# design.net
KiCad netlist of a schematic drawn in Altium Designer
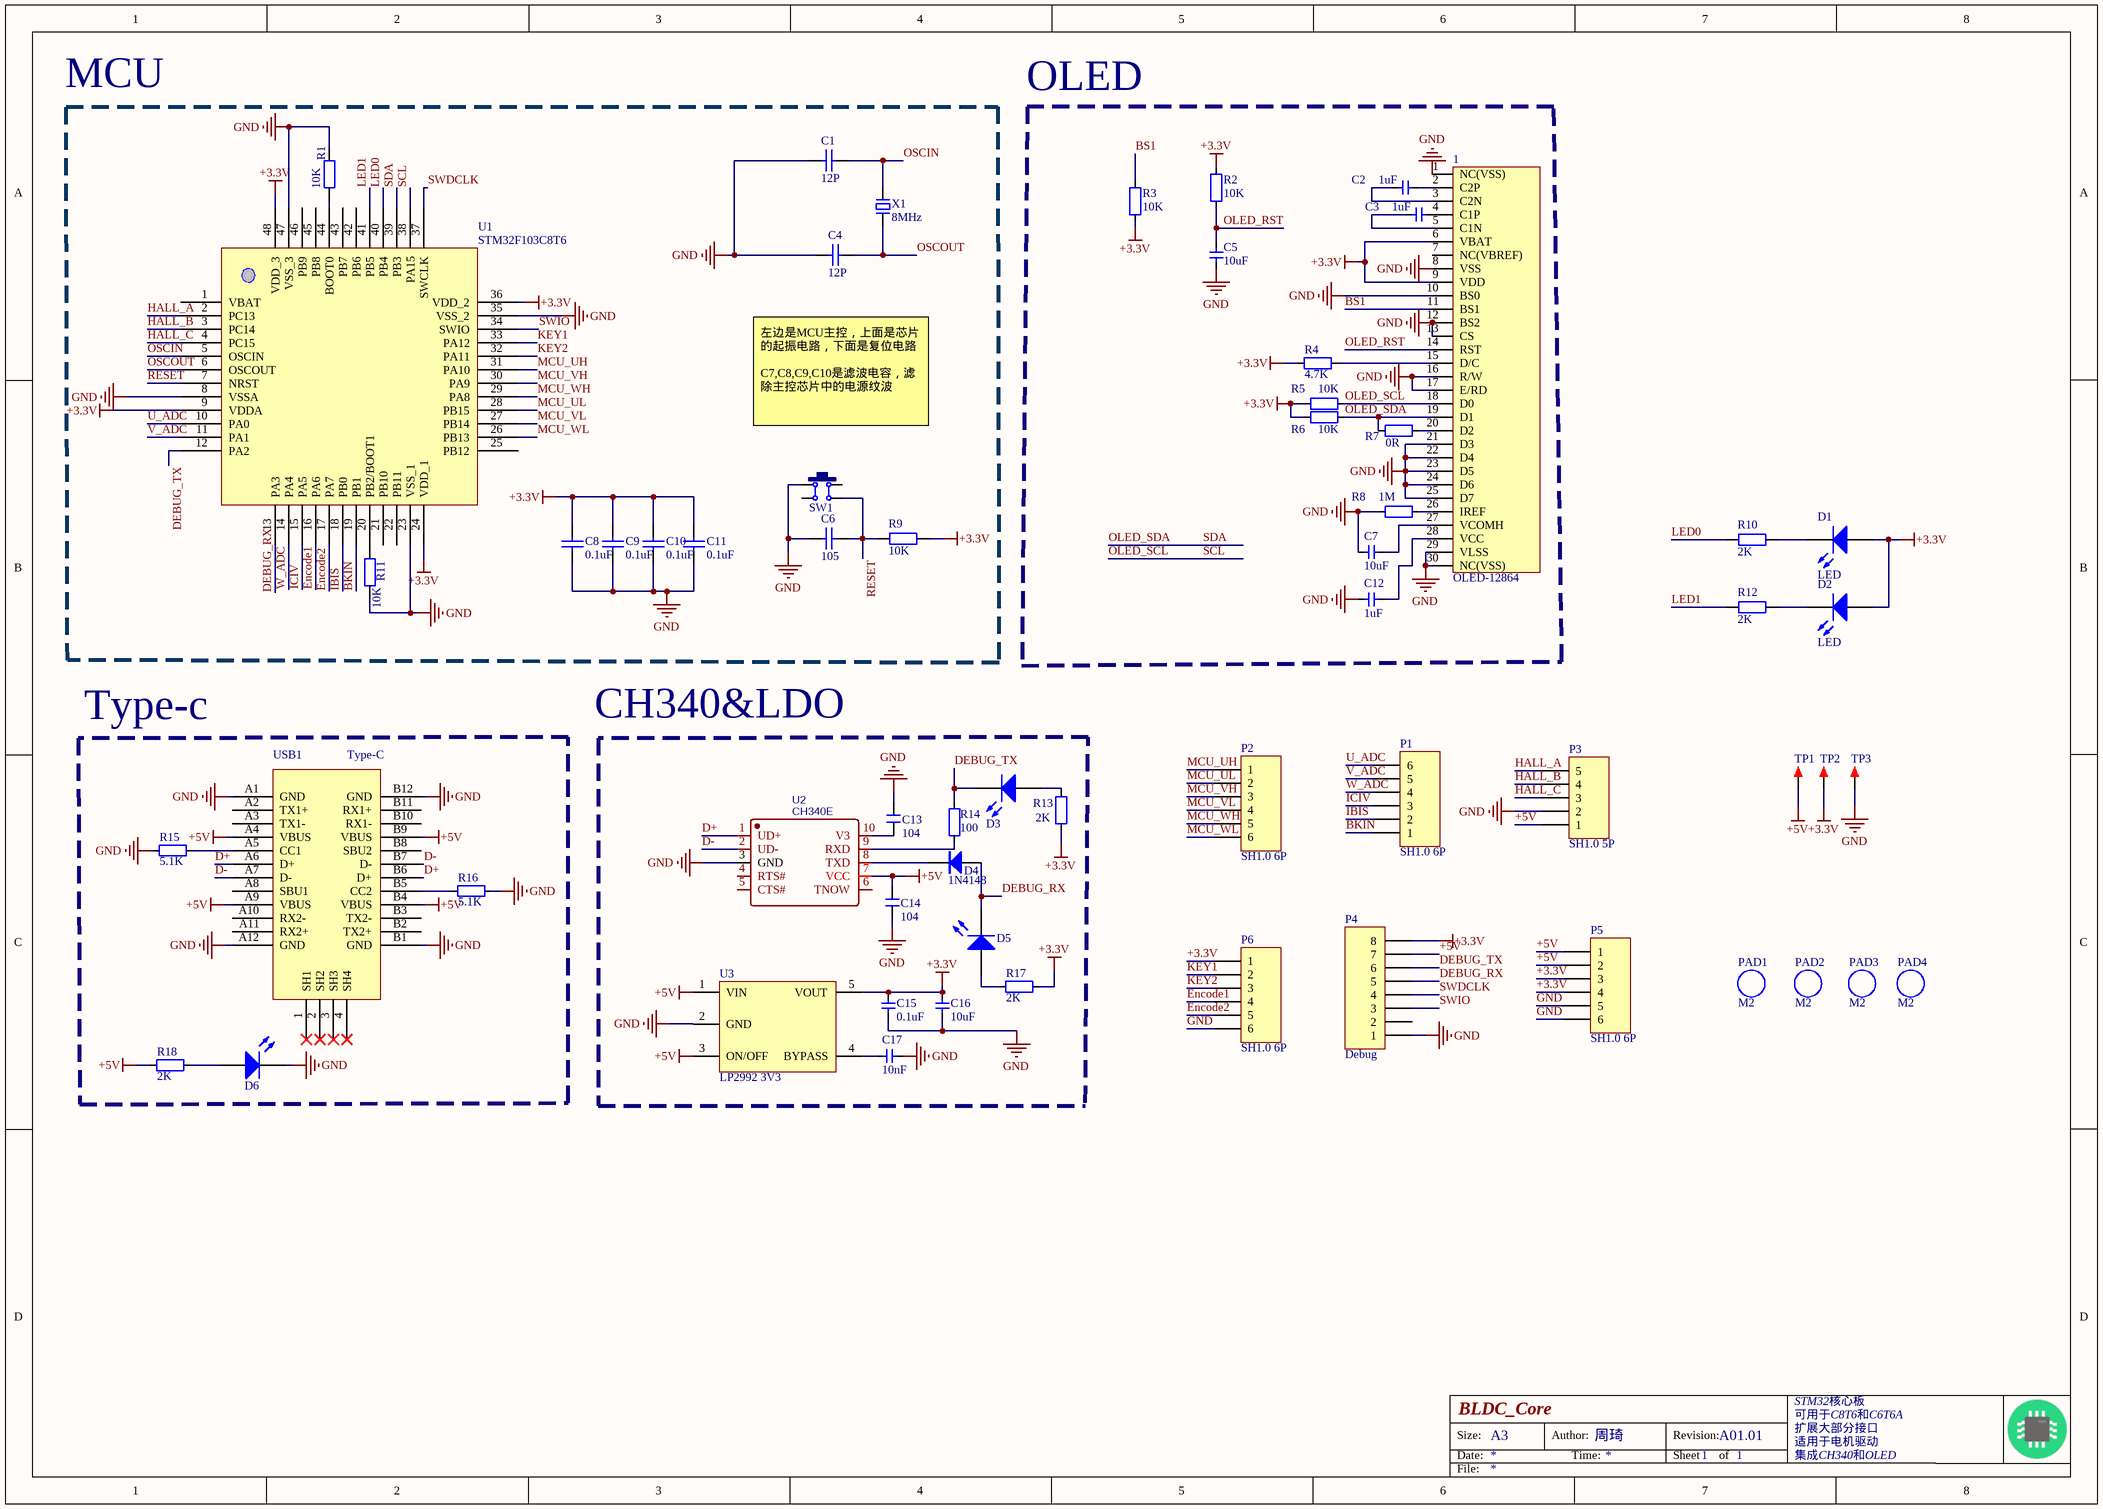
[diagram p0: 原理图.SchDoc]

(export (version "E")
  (design (tool "Eeschema 10.0.6"))
  (components
    (comp (ref "1")
      (value "OLED-12864")
      (footprint "OLED-12864-1.3-TOP")
      (description "显示屏")
      (libsource (lib "MyPcbLib") (part "OLED-12864"))
    )
    (comp (ref "C1")
      (value "12P")
      (footprint "C0603_M")
      (description "贴片电容")
      (libsource (lib "0.1 - 电阻-电容-电感-磁珠-电位器") (part "C"))
    )
    (comp (ref "C2")
      (value "1uF")
      (footprint "C0402_L")
      (description "Capacitor")
      (libsource (lib "MyPcbLib") (part "电容-0402"))
    )
    (comp (ref "C3")
      (value "1uF")
      (footprint "C0402_L")
      (description "Capacitor")
      (libsource (lib "MyPcbLib") (part "电容-0402"))
    )
    (comp (ref "C4")
      (value "12P")
      (footprint "C0603_M")
      (description "贴片电容")
      (libsource (lib "0.1 - 电阻-电容-电感-磁珠-电位器") (part "C"))
    )
    (comp (ref "C5")
      (value "10uF")
      (footprint "C0402_L")
      (description "Capacitor")
      (libsource (lib "MyPcbLib") (part "电容-0402"))
    )
    (comp (ref "C6")
      (value "105")
      (footprint "C0402_L")
      (description "贴片电容")
      (libsource (lib "0.1 - 电阻-电容-电感-磁珠-电位器") (part "C"))
    )
    (comp (ref "C7")
      (value "10uF")
      (footprint "C0402_L")
      (description "Capacitor")
      (libsource (lib "MyPcbLib") (part "电容-0402"))
    )
    (comp (ref "C8")
      (value "0.1uF")
      (footprint "C0402_L")
      (description "贴片电容")
      (libsource (lib "0.1 - 电阻-电容-电感-磁珠-电位器") (part "C"))
    )
    (comp (ref "C9")
      (value "0.1uF")
      (footprint "C0402_L")
      (description "贴片电容")
      (libsource (lib "0.1 - 电阻-电容-电感-磁珠-电位器") (part "C"))
    )
    (comp (ref "C10")
      (value "0.1uF")
      (footprint "C0402_L")
      (description "贴片电容")
      (libsource (lib "0.1 - 电阻-电容-电感-磁珠-电位器") (part "C"))
    )
    (comp (ref "C11")
      (value "0.1uF")
      (footprint "C0402_L")
      (description "贴片电容")
      (libsource (lib "0.1 - 电阻-电容-电感-磁珠-电位器") (part "C"))
    )
    (comp (ref "C12")
      (value "1uF")
      (footprint "C0402_L")
      (description "Capacitor")
      (libsource (lib "MyPcbLib") (part "电容-0402"))
    )
    (comp (ref "C13")
      (value "104")
      (footprint "C0402_L")
      (description "无极性贴片电容")
      (fields (field (name "版权归属") "源创客"))
      (libsource (lib "9-电阻-电容-电感") (part "C"))
    )
    (comp (ref "C14")
      (value "104")
      (footprint "C0402_L")
      (description "无极性贴片电容")
      (fields (field (name "版权归属") "源创客"))
      (libsource (lib "9-电阻-电容-电感") (part "C"))
    )
    (comp (ref "C15")
      (value "0.1uF")
      (footprint "C0402_L")
      (description "Capacitor")
      (libsource (lib "MyPcbLib") (part "电容-0402"))
    )
    (comp (ref "C16")
      (value "10uF")
      (footprint "C0402_L")
      (description "Capacitor")
      (libsource (lib "MyPcbLib") (part "电容-0402"))
    )
    (comp (ref "C17")
      (value "10nF")
      (footprint "C0402_L")
      (description "Capacitor")
      (libsource (lib "MyPcbLib") (part "电容-0402"))
    )
    (comp (ref "D1")
      (value "LED")
      (footprint "LED0603_B")
      (description "发光二极管")
      (libsource (lib "0.3 - LED发光二极管") (part "LED"))
    )
    (comp (ref "D2")
      (value "LED")
      (footprint "LED0603_B")
      (description "发光二极管")
      (libsource (lib "0.3 - LED发光二极管") (part "LED"))
    )
    (comp (ref "D3")
      (value "LED0")
      (footprint "LED0603_G")
      (description "发光二极管")
      (fields (field (name "PUBLISHER") "Altium Limited"))
      (libsource (lib "18-常用器件") (part "LED0"))
    )
    (comp (ref "D4")
      (value "1N4148")
      (footprint "SOD-123")
      (description "整流二极管")
      (fields (field (name "版权归属") "源创客"))
      (libsource (lib "10-二极管-整流桥") (part "M7"))
    )
    (comp (ref "D5")
      (value "LED0")
      (footprint "LED0603_G")
      (description "发光二极管")
      (fields (field (name "PUBLISHER") "Altium Limited"))
      (libsource (lib "18-常用器件") (part "LED0"))
    )
    (comp (ref "D6")
      (value "LED0")
      (footprint "LED0603_R")
      (description "发光二极管")
      (fields (field (name "PUBLISHER") "Altium Limited"))
      (libsource (lib "18-常用器件") (part "LED0"))
    )
    (comp (ref "P1")
      (value "SH1.0 6P")
      (footprint "SH 1.0-WS-6P")
      (description "Header, 6-Pin")
      (fields (field (name "PUBLISHER") "Altium Limited"))
      (libsource (lib "") (part "Header 6_1"))
    )
    (comp (ref "P2")
      (value "SH1.0 6P")
      (footprint "SH 1.0-WS-6P")
      (description "Header, 6-Pin")
      (fields (field (name "PUBLISHER") "Altium Limited"))
      (libsource (lib "Miscellaneous Connectors") (part "Header 6"))
    )
    (comp (ref "P3")
      (value "SH1.0 5P")
      (footprint "SH 1.0-LS-5P")
      (description "Header, 5-Pin")
      (fields (field (name "PUBLISHER") "Altium Limited"))
      (libsource (lib "Miscellaneous Connectors") (part "Header 5"))
    )
    (comp (ref "P4")
      (value "Debug")
      (footprint "FPC0.5 2H-WS-8P")
      (description "Header, 8-Pin")
      (fields (field (name "PUBLISHER") "Altium Limited"))
      (libsource (lib "Miscellaneous Connectors") (part "Header 8"))
    )
    (comp (ref "P5")
      (value "SH1.0 6P")
      (footprint "SH 1.0-WS-6P")
      (description "Header, 6-Pin")
      (fields (field (name "PUBLISHER") "Altium Limited"))
      (libsource (lib "Miscellaneous Connectors") (part "Header 6"))
    )
    (comp (ref "P6")
      (value "SH1.0 6P")
      (footprint "SH 1.0-WS-6P")
      (description "Header, 6-Pin")
      (fields (field (name "PUBLISHER") "Altium Limited"))
      (libsource (lib "Miscellaneous Connectors") (part "Header 6"))
    )
    (comp (ref "PAD1")
      (value "M2")
      (footprint "M2")
      (description "铜柱孔")
      (libsource (lib "0.7 - 常用按键-开关-蜂鸣器-电池-测试点") (part "M3"))
    )
    (comp (ref "PAD2")
      (value "M2")
      (footprint "M2")
      (description "铜柱孔")
      (libsource (lib "0.7 - 常用按键-开关-蜂鸣器-电池-测试点") (part "M3"))
    )
    (comp (ref "PAD3")
      (value "M2")
      (footprint "M2")
      (description "铜柱孔")
      (libsource (lib "0.7 - 常用按键-开关-蜂鸣器-电池-测试点") (part "M3"))
    )
    (comp (ref "PAD4")
      (value "M2")
      (footprint "M2")
      (description "铜柱孔")
      (libsource (lib "0.7 - 常用按键-开关-蜂鸣器-电池-测试点") (part "M3"))
    )
    (comp (ref "R1")
      (value "10K")
      (footprint "R0402_L")
      (description "贴片电阻")
      (libsource (lib "0.1 - 电阻-电容-电感-磁珠-电位器") (part "R"))
    )
    (comp (ref "R2")
      (value "10K")
      (footprint "R0402_L")
      (description "Resistor")
      (libsource (lib "") (part "电阻-0402_2"))
    )
    (comp (ref "R3")
      (value "10K")
      (footprint "R0402_L")
      (description "Resistor")
      (libsource (lib "") (part "电阻-0402_2"))
    )
    (comp (ref "R4")
      (value "4.7K")
      (footprint "R0402_L")
      (description "Resistor")
      (libsource (lib "") (part "电阻-0402_1"))
    )
    (comp (ref "R5")
      (value "10K")
      (footprint "R0402_L")
      (description "Resistor")
      (libsource (lib "MyPcbLib") (part "电阻-0402"))
    )
    (comp (ref "R6")
      (value "10K")
      (footprint "R0402_L")
      (description "Resistor")
      (libsource (lib "MyPcbLib") (part "电阻-0402"))
    )
    (comp (ref "R7")
      (value "0R")
      (footprint "R0402_L")
      (description "Resistor")
      (libsource (lib "") (part "电阻-0402_1"))
    )
    (comp (ref "R8")
      (value "1M")
      (footprint "R0402_L")
      (description "Resistor")
      (libsource (lib "MyPcbLib") (part "电阻-0402"))
    )
    (comp (ref "R9")
      (value "10K")
      (footprint "R0402_L")
      (description "贴片电阻")
      (libsource (lib "0.1 - 电阻-电容-电感-磁珠-电位器") (part "R"))
    )
    (comp (ref "R10")
      (value "2K")
      (footprint "R0402_L")
      (description "贴片电阻")
      (libsource (lib "0.1 - 电阻-电容-电感-磁珠-电位器") (part "R"))
    )
    (comp (ref "R11")
      (value "10K")
      (footprint "R0402_L")
      (description "贴片电阻")
      (libsource (lib "0.1 - 电阻-电容-电感-磁珠-电位器") (part "R"))
    )
    (comp (ref "R12")
      (value "2K")
      (footprint "R0402_L")
      (description "贴片电阻")
      (libsource (lib "0.1 - 电阻-电容-电感-磁珠-电位器") (part "R"))
    )
    (comp (ref "R13")
      (value "2K")
      (footprint "R0402_L")
      (description "Resistor")
      (libsource (lib "") (part "电阻-0402_2"))
    )
    (comp (ref "R14")
      (value "100")
      (footprint "R0402_L")
      (description "Resistor")
      (libsource (lib "") (part "电阻-0402_3"))
    )
    (comp (ref "R15")
      (value "5.1K")
      (footprint "R0402_L")
      (description "Resistor")
      (libsource (lib "MyPcbLib") (part "电阻-0402"))
    )
    (comp (ref "R16")
      (value "5.1K")
      (footprint "R0402_L")
      (description "Resistor")
      (libsource (lib "") (part "电阻-0402_1"))
    )
    (comp (ref "R17")
      (value "2K")
      (footprint "R0402_L")
      (description "Resistor")
      (libsource (lib "") (part "电阻-0402_1"))
    )
    (comp (ref "R18")
      (value "2K")
      (footprint "R0402_L")
      (description "Resistor")
      (libsource (lib "MyPcbLib") (part "电阻-0402"))
    )
    (comp (ref "SW1")
      (value "6x6x5")
      (footprint "TSW SMD-4*4*1.5")
      (description "贴片6x6轻触开关")
      (fields (field (name "版权归属") "源创客"))
      (libsource (lib "5-按键-开关") (part "TSW SMD-6x6"))
    )
    (comp (ref "TP1")
      (value "TEST")
      (footprint "TEST 1.6")
      (description "测试点")
      (libsource (lib "0.7 - 常用按键-开关-蜂鸣器-电池-测试点") (part "TEST"))
    )
    (comp (ref "TP2")
      (value "TEST")
      (footprint "TEST 1.6")
      (description "测试点")
      (libsource (lib "0.7 - 常用按键-开关-蜂鸣器-电池-测试点") (part "TEST"))
    )
    (comp (ref "TP3")
      (value "TEST")
      (footprint "TEST 1.6")
      (description "测试点")
      (libsource (lib "0.7 - 常用按键-开关-蜂鸣器-电池-测试点") (part "TEST"))
    )
    (comp (ref "U1")
      (value "STM32F103C8T6")
      (footprint "LQFP48-7*7")
      (libsource (lib "STM32F103C8T6") (part "STM32F103C8T6"))
    )
    (comp (ref "U2")
      (value "CH340E")
      (footprint "MSOP10_M")
      (fields (field (name "BOM_SUPPLIER PART") "C99652") (field (name "SUBPART_NO") "1"))
      (libsource (lib "altium-import") (part "root_0_CH340E_"))
    )
    (comp (ref "U3")
      (value "LP2992 3V3")
      (footprint "SOT23-5")
      (description "LDO")
      (libsource (lib "MyPcbLib") (part "LP2992"))
    )
    (comp (ref "USB1")
      (value "Type-C")
      (footprint "USB-C-SMD_16P")
      (libsource (lib "MyPcbLib") (part "USB-Type-C-TOP"))
    )
    (comp (ref "X1")
      (value "8MHz")
      (footprint "OSC 4025-4P")
      (description "2脚无源脚晶振")
      (libsource (lib "0.5 - 保险丝-晶振-光耦") (part "XTAL-2P"))
    )
  )
  (nets
    (net (code "1") (name "+3.3V") (class "Default")
      (node (ref "1") (pin "6") (pinfunction "VBAT_6") (pintype "passive"))
      (node (ref "1") (pin "9") (pinfunction "VDD_9") (pintype "passive"))
      (node (ref "C10") (pin "1") (pinfunction "1_1") (pintype "passive"))
      (node (ref "C11") (pin "1") (pinfunction "1_1") (pintype "passive"))
      (node (ref "C15") (pin "2") (pinfunction "2_2") (pintype "passive"))
      (node (ref "C16") (pin "2") (pinfunction "2_2") (pintype "passive"))
      (node (ref "C8") (pin "1") (pinfunction "1_1") (pintype "passive"))
      (node (ref "C9") (pin "1") (pinfunction "1_1") (pintype "passive"))
      (node (ref "D1") (pin "1") (pinfunction "A_1") (pintype "passive"))
      (node (ref "D2") (pin "1") (pinfunction "A_1") (pintype "passive"))
      (node (ref "P4") (pin "8") (pinfunction "8_8") (pintype "passive"))
      (node (ref "P5") (pin "3") (pinfunction "3_3") (pintype "passive"))
      (node (ref "P5") (pin "4") (pinfunction "4_4") (pintype "passive"))
      (node (ref "P6") (pin "1") (pinfunction "1_1") (pintype "passive"))
      (node (ref "R13") (pin "1") (pinfunction "1_1") (pintype "passive"))
      (node (ref "R17") (pin "1") (pinfunction "1_1") (pintype "passive"))
      (node (ref "R2") (pin "2") (pinfunction "2_2") (pintype "passive"))
      (node (ref "R3") (pin "1") (pinfunction "1_1") (pintype "passive"))
      (node (ref "R4") (pin "2") (pinfunction "2_2") (pintype "passive"))
      (node (ref "R5") (pin "1") (pinfunction "1_1") (pintype "passive"))
      (node (ref "R6") (pin "1") (pinfunction "1_1") (pintype "passive"))
      (node (ref "R9") (pin "2") (pinfunction "2_2") (pintype "passive"))
      (node (ref "TP2") (pin "1") (pinfunction "1_1") (pintype "passive"))
      (node (ref "U1") (pin "24") (pinfunction "VDD_1_24") (pintype "passive"))
      (node (ref "U1") (pin "36") (pinfunction "VDD_2_36") (pintype "passive"))
      (node (ref "U1") (pin "48") (pinfunction "VDD_3_48") (pintype "passive"))
      (node (ref "U1") (pin "9") (pinfunction "VDDA_9") (pintype "passive"))
      (node (ref "U3") (pin "5") (pinfunction "VOUT_5") (pintype "passive"))
    )
    (net (code "2") (name "+5V") (class "Default")
      (node (ref "C14") (pin "1") (pinfunction "1_1") (pintype "passive"))
      (node (ref "P3") (pin "1") (pinfunction "1_1") (pintype "passive"))
      (node (ref "P4") (pin "7") (pinfunction "7_7") (pintype "passive"))
      (node (ref "P5") (pin "1") (pinfunction "1_1") (pintype "passive"))
      (node (ref "P5") (pin "2") (pinfunction "2_2") (pintype "passive"))
      (node (ref "R18") (pin "1") (pinfunction "1_1") (pintype "passive"))
      (node (ref "TP1") (pin "1") (pinfunction "1_1") (pintype "passive"))
      (node (ref "U2") (pin "7") (pinfunction "VCC_7") (pintype "passive"))
      (node (ref "U3") (pin "1") (pinfunction "VIN_1") (pintype "passive"))
      (node (ref "U3") (pin "3") (pinfunction "ON/OFF_3") (pintype "passive"))
      (node (ref "USB1") (pin "A4") (pinfunction "VBUS_A4") (pintype "passive"))
      (node (ref "USB1") (pin "A9") (pinfunction "VBUS_A9") (pintype "passive"))
      (node (ref "USB1") (pin "B4") (pinfunction "VBUS_B4") (pintype "passive"))
      (node (ref "USB1") (pin "B9") (pinfunction "VBUS_B9") (pintype "passive"))
    )
    (net (code "3") (name "/BKIN") (class "Default")
      (node (ref "P1") (pin "1") (pinfunction "1_1") (pintype "passive"))
      (node (ref "U1") (pin "19") (pinfunction "PB1_19") (pintype "passive"))
    )
    (net (code "4") (name "/BS1") (class "Default")
      (node (ref "1") (pin "11") (pinfunction "BS1_11") (pintype "passive"))
      (node (ref "R3") (pin "2") (pinfunction "2_2") (pintype "passive"))
    )
    (net (code "5") (name "/D+") (class "Default")
      (node (ref "U2") (pin "1") (pinfunction "UD+_1") (pintype "passive"))
      (node (ref "USB1") (pin "A6") (pinfunction "D+_A6") (pintype "passive"))
      (node (ref "USB1") (pin "B6") (pinfunction "D+_B6") (pintype "passive"))
    )
    (net (code "6") (name "/D-") (class "Default")
      (node (ref "U2") (pin "2") (pinfunction "UD-_2") (pintype "passive"))
      (node (ref "USB1") (pin "A7") (pinfunction "D-_A7") (pintype "passive"))
      (node (ref "USB1") (pin "B7") (pinfunction "D-_B7") (pintype "passive"))
    )
    (net (code "7") (name "/DEBUG_RX") (class "Default")
      (node (ref "D4") (pin "1") (pinfunction "A_1") (pintype "passive"))
      (node (ref "D5") (pin "2") (pinfunction "K_2") (pintype "passive"))
      (node (ref "P4") (pin "5") (pinfunction "5_5") (pintype "passive"))
      (node (ref "U1") (pin "13") (pinfunction "PA3_13") (pintype "passive"))
    )
    (net (code "8") (name "/DEBUG_TX") (class "Default")
      (node (ref "D3") (pin "2") (pinfunction "K_2") (pintype "passive"))
      (node (ref "P4") (pin "6") (pinfunction "6_6") (pintype "passive"))
      (node (ref "R14") (pin "1") (pinfunction "1_1") (pintype "passive"))
      (node (ref "U1") (pin "12") (pinfunction "PA2_12") (pintype "passive"))
    )
    (net (code "9") (name "/Encode1") (class "Default")
      (node (ref "P6") (pin "4") (pinfunction "4_4") (pintype "passive"))
      (node (ref "U1") (pin "16") (pinfunction "PA6_16") (pintype "passive"))
    )
    (net (code "10") (name "/Encode2") (class "Default")
      (node (ref "P6") (pin "5") (pinfunction "5_5") (pintype "passive"))
      (node (ref "U1") (pin "17") (pinfunction "PA7_17") (pintype "passive"))
    )
    (net (code "11") (name "/HALL_A") (class "Default")
      (node (ref "P3") (pin "5") (pinfunction "5_5") (pintype "passive"))
      (node (ref "U1") (pin "2") (pinfunction "PC13_2") (pintype "passive"))
    )
    (net (code "12") (name "/HALL_B") (class "Default")
      (node (ref "P3") (pin "4") (pinfunction "4_4") (pintype "passive"))
      (node (ref "U1") (pin "3") (pinfunction "PC14_3") (pintype "passive"))
    )
    (net (code "13") (name "/HALL_C") (class "Default")
      (node (ref "P3") (pin "3") (pinfunction "3_3") (pintype "passive"))
      (node (ref "U1") (pin "4") (pinfunction "PC15_4") (pintype "passive"))
    )
    (net (code "14") (name "/IBIS") (class "Default")
      (node (ref "P1") (pin "2") (pinfunction "2_2") (pintype "passive"))
      (node (ref "U1") (pin "18") (pinfunction "PB0_18") (pintype "passive"))
    )
    (net (code "15") (name "/ICIV") (class "Default")
      (node (ref "P1") (pin "3") (pinfunction "3_3") (pintype "passive"))
      (node (ref "U1") (pin "15") (pinfunction "PA5_15") (pintype "passive"))
    )
    (net (code "16") (name "/KEY1") (class "Default")
      (node (ref "P6") (pin "2") (pinfunction "2_2") (pintype "passive"))
      (node (ref "U1") (pin "33") (pinfunction "PA12_33") (pintype "passive"))
    )
    (net (code "17") (name "/KEY2") (class "Default")
      (node (ref "P6") (pin "3") (pinfunction "3_3") (pintype "passive"))
      (node (ref "U1") (pin "32") (pinfunction "PA11_32") (pintype "passive"))
    )
    (net (code "18") (name "/LED0") (class "Default")
      (node (ref "R10") (pin "2") (pinfunction "2_2") (pintype "passive"))
      (node (ref "U1") (pin "40") (pinfunction "PB4_40") (pintype "passive"))
    )
    (net (code "19") (name "/LED1") (class "Default")
      (node (ref "R12") (pin "2") (pinfunction "2_2") (pintype "passive"))
      (node (ref "U1") (pin "41") (pinfunction "PB5_41") (pintype "passive"))
    )
    (net (code "20") (name "/MCU_UH") (class "Default")
      (node (ref "P2") (pin "1") (pinfunction "1_1") (pintype "passive"))
      (node (ref "U1") (pin "31") (pinfunction "PA10_31") (pintype "passive"))
    )
    (net (code "21") (name "/MCU_UL") (class "Default")
      (node (ref "P2") (pin "2") (pinfunction "2_2") (pintype "passive"))
      (node (ref "U1") (pin "28") (pinfunction "PB15_28") (pintype "passive"))
    )
    (net (code "22") (name "/MCU_VH") (class "Default")
      (node (ref "P2") (pin "3") (pinfunction "3_3") (pintype "passive"))
      (node (ref "U1") (pin "30") (pinfunction "PA9_30") (pintype "passive"))
    )
    (net (code "23") (name "/MCU_VL") (class "Default")
      (node (ref "P2") (pin "4") (pinfunction "4_4") (pintype "passive"))
      (node (ref "U1") (pin "27") (pinfunction "PB14_27") (pintype "passive"))
    )
    (net (code "24") (name "/MCU_WH") (class "Default")
      (node (ref "P2") (pin "5") (pinfunction "5_5") (pintype "passive"))
      (node (ref "U1") (pin "29") (pinfunction "PA8_29") (pintype "passive"))
    )
    (net (code "25") (name "/MCU_WL") (class "Default")
      (node (ref "P2") (pin "6") (pinfunction "6_6") (pintype "passive"))
      (node (ref "U1") (pin "26") (pinfunction "PB13_26") (pintype "passive"))
    )
    (net (code "26") (name "/OLED_RST") (class "Default")
      (node (ref "1") (pin "14") (pinfunction "RST_14") (pintype "passive"))
      (node (ref "C5") (pin "2") (pinfunction "2_2") (pintype "passive"))
      (node (ref "R2") (pin "1") (pinfunction "1_1") (pintype "passive"))
    )
    (net (code "27") (name "/OLED_SCL") (class "Default")
      (node (ref "1") (pin "18") (pinfunction "D0_18") (pintype "passive"))
      (node (ref "R5") (pin "2") (pinfunction "2_2") (pintype "passive"))
      (node (ref "U1") (pin "38") (pinfunction "PA15_38") (pintype "passive"))
    )
    (net (code "28") (name "/OLED_SDA") (class "Default")
      (node (ref "1") (pin "19") (pinfunction "D1_19") (pintype "passive"))
      (node (ref "R6") (pin "2") (pinfunction "2_2") (pintype "passive"))
      (node (ref "R7") (pin "2") (pinfunction "2_2") (pintype "passive"))
      (node (ref "U1") (pin "39") (pinfunction "PB3_39") (pintype "passive"))
    )
    (net (code "29") (name "/OSCIN") (class "Default")
      (node (ref "C1") (pin "2") (pinfunction "2_2") (pintype "passive"))
      (node (ref "U1") (pin "5") (pinfunction "OSCIN_5") (pintype "passive"))
      (node (ref "X1") (pin "3") (pinfunction "3_3") (pintype "passive"))
    )
    (net (code "30") (name "/OSCOUT") (class "Default")
      (node (ref "C4") (pin "2") (pinfunction "2_2") (pintype "passive"))
      (node (ref "U1") (pin "6") (pinfunction "OSCOUT_6") (pintype "passive"))
      (node (ref "X1") (pin "1") (pinfunction "1_1") (pintype "passive"))
    )
    (net (code "31") (name "/RESET") (class "Default")
      (node (ref "C6") (pin "2") (pinfunction "2_2") (pintype "passive"))
      (node (ref "R9") (pin "1") (pinfunction "1_1") (pintype "passive"))
      (node (ref "SW1") (pin "3") (pinfunction "3_3") (pintype "passive"))
      (node (ref "U1") (pin "7") (pinfunction "NRST_7") (pintype "passive"))
    )
    (net (code "32") (name "/SWDCLK") (class "Default")
      (node (ref "P4") (pin "4") (pinfunction "4_4") (pintype "passive"))
      (node (ref "U1") (pin "37") (pinfunction "SWCLK_37") (pintype "passive"))
    )
    (net (code "33") (name "/SWIO") (class "Default")
      (node (ref "P4") (pin "3") (pinfunction "3_3") (pintype "passive"))
      (node (ref "U1") (pin "34") (pinfunction "SWIO_34") (pintype "passive"))
    )
    (net (code "34") (name "/U_ADC") (class "Default")
      (node (ref "P1") (pin "6") (pinfunction "6_6") (pintype "passive"))
      (node (ref "U1") (pin "10") (pinfunction "PA0_10") (pintype "passive"))
    )
    (net (code "35") (name "/V_ADC") (class "Default")
      (node (ref "P1") (pin "5") (pinfunction "5_5") (pintype "passive"))
      (node (ref "U1") (pin "11") (pinfunction "PA1_11") (pintype "passive"))
    )
    (net (code "36") (name "/W_ADC") (class "Default")
      (node (ref "P1") (pin "4") (pinfunction "4_4") (pintype "passive"))
      (node (ref "U1") (pin "14") (pinfunction "PA4_14") (pintype "passive"))
    )
    (net (code "37") (name "GND") (class "Default")
      (node (ref "1") (pin "1") (pinfunction "NC(VSS)_1") (pintype "passive"))
      (node (ref "1") (pin "10") (pinfunction "BS0_10") (pintype "passive"))
      (node (ref "1") (pin "12") (pinfunction "BS2_12") (pintype "passive"))
      (node (ref "1") (pin "13") (pinfunction "CS_13") (pintype "passive"))
      (node (ref "1") (pin "16") (pinfunction "R/W_16") (pintype "passive"))
      (node (ref "1") (pin "17") (pinfunction "E/RD_17") (pintype "passive"))
      (node (ref "1") (pin "21") (pinfunction "D3_21") (pintype "passive"))
      (node (ref "1") (pin "22") (pinfunction "D4_22") (pintype "passive"))
      (node (ref "1") (pin "23") (pinfunction "D5_23") (pintype "passive"))
      (node (ref "1") (pin "24") (pinfunction "D6_24") (pintype "passive"))
      (node (ref "1") (pin "25") (pinfunction "D7_25") (pintype "passive"))
      (node (ref "1") (pin "29") (pinfunction "VLSS_29") (pintype "passive"))
      (node (ref "1") (pin "30") (pinfunction "NC(VSS)_30") (pintype "passive"))
      (node (ref "1") (pin "8") (pinfunction "VSS_8") (pintype "passive"))
      (node (ref "C1") (pin "1") (pinfunction "1_1") (pintype "passive"))
      (node (ref "C10") (pin "2") (pinfunction "2_2") (pintype "passive"))
      (node (ref "C11") (pin "2") (pinfunction "2_2") (pintype "passive"))
      (node (ref "C12") (pin "2") (pinfunction "2_2") (pintype "passive"))
      (node (ref "C13") (pin "1") (pinfunction "1_1") (pintype "passive"))
      (node (ref "C14") (pin "2") (pinfunction "2_2") (pintype "passive"))
      (node (ref "C15") (pin "1") (pinfunction "1_1") (pintype "passive"))
      (node (ref "C16") (pin "1") (pinfunction "1_1") (pintype "passive"))
      (node (ref "C17") (pin "1") (pinfunction "1_1") (pintype "passive"))
      (node (ref "C4") (pin "1") (pinfunction "1_1") (pintype "passive"))
      (node (ref "C5") (pin "1") (pinfunction "1_1") (pintype "passive"))
      (node (ref "C6") (pin "1") (pinfunction "1_1") (pintype "passive"))
      (node (ref "C7") (pin "2") (pinfunction "2_2") (pintype "passive"))
      (node (ref "C8") (pin "2") (pinfunction "2_2") (pintype "passive"))
      (node (ref "C9") (pin "2") (pinfunction "2_2") (pintype "passive"))
      (node (ref "D6") (pin "2") (pinfunction "K_2") (pintype "passive"))
      (node (ref "P3") (pin "2") (pinfunction "2_2") (pintype "passive"))
      (node (ref "P4") (pin "1") (pinfunction "1_1") (pintype "passive"))
      (node (ref "P5") (pin "5") (pinfunction "5_5") (pintype "passive"))
      (node (ref "P5") (pin "6") (pinfunction "6_6") (pintype "passive"))
      (node (ref "P6") (pin "6") (pinfunction "6_6") (pintype "passive"))
      (node (ref "R1") (pin "2") (pinfunction "2_2") (pintype "passive"))
      (node (ref "R11") (pin "1") (pinfunction "1_1") (pintype "passive"))
      (node (ref "R15") (pin "1") (pinfunction "1_1") (pintype "passive"))
      (node (ref "R16") (pin "1") (pinfunction "1_1") (pintype "passive"))
      (node (ref "R8") (pin "1") (pinfunction "1_1") (pintype "passive"))
      (node (ref "SW1") (pin "1") (pinfunction "1_1") (pintype "passive"))
      (node (ref "TP3") (pin "1") (pinfunction "1_1") (pintype "passive"))
      (node (ref "U1") (pin "23") (pinfunction "VSS_1_23") (pintype "passive"))
      (node (ref "U1") (pin "35") (pinfunction "VSS_2_35") (pintype "passive"))
      (node (ref "U1") (pin "47") (pinfunction "VSS_3_47") (pintype "passive"))
      (node (ref "U1") (pin "8") (pinfunction "VSSA_8") (pintype "passive"))
      (node (ref "U2") (pin "3") (pinfunction "GND_3") (pintype "passive"))
      (node (ref "U3") (pin "2") (pinfunction "GND_2") (pintype "passive"))
      (node (ref "USB1") (pin "A1") (pinfunction "GND_A1") (pintype "passive"))
      (node (ref "USB1") (pin "A12") (pinfunction "GND_A12") (pintype "passive"))
      (node (ref "USB1") (pin "B1") (pinfunction "GND_B1") (pintype "passive"))
      (node (ref "USB1") (pin "B12") (pinfunction "GND_B12") (pintype "passive"))
    )
    (net (code "38") (name "Net-(1-C1N)") (class "Default")
      (node (ref "1") (pin "5") (pinfunction "C1N_5") (pintype "passive"))
      (node (ref "C3") (pin "2") (pinfunction "2_2") (pintype "passive"))
    )
    (net (code "39") (name "Net-(1-C1P)") (class "Default")
      (node (ref "1") (pin "4") (pinfunction "C1P_4") (pintype "passive"))
      (node (ref "C3") (pin "1") (pinfunction "1_1") (pintype "passive"))
    )
    (net (code "40") (name "Net-(1-C2N)") (class "Default")
      (node (ref "1") (pin "3") (pinfunction "C2N_3") (pintype "passive"))
      (node (ref "C2") (pin "2") (pinfunction "2_2") (pintype "passive"))
    )
    (net (code "41") (name "Net-(1-C2P)") (class "Default")
      (node (ref "1") (pin "2") (pinfunction "C2P_2") (pintype "passive"))
      (node (ref "C2") (pin "1") (pinfunction "1_1") (pintype "passive"))
    )
    (net (code "42") (name "Net-(1-D2)") (class "Default")
      (node (ref "1") (pin "20") (pinfunction "D2_20") (pintype "passive"))
      (node (ref "R7") (pin "1") (pinfunction "1_1") (pintype "passive"))
    )
    (net (code "43") (name "Net-(1-D{slash}C)") (class "Default")
      (node (ref "1") (pin "15") (pinfunction "D/C_15") (pintype "passive"))
      (node (ref "R4") (pin "1") (pinfunction "1_1") (pintype "passive"))
    )
    (net (code "44") (name "Net-(1-IREF)") (class "Default")
      (node (ref "1") (pin "26") (pinfunction "IREF_26") (pintype "passive"))
      (node (ref "R8") (pin "2") (pinfunction "2_2") (pintype "passive"))
    )
    (net (code "45") (name "Net-(1-VCC)") (class "Default")
      (node (ref "1") (pin "28") (pinfunction "VCC_28") (pintype "passive"))
      (node (ref "C12") (pin "1") (pinfunction "1_1") (pintype "passive"))
    )
    (net (code "46") (name "Net-(1-VCOMH)") (class "Default")
      (node (ref "1") (pin "27") (pinfunction "VCOMH_27") (pintype "passive"))
      (node (ref "C7") (pin "1") (pinfunction "1_1") (pintype "passive"))
    )
    (net (code "47") (name "Net-(D1-K)") (class "Default")
      (node (ref "D1") (pin "2") (pinfunction "K_2") (pintype "passive"))
      (node (ref "R10") (pin "1") (pinfunction "1_1") (pintype "passive"))
    )
    (net (code "48") (name "Net-(D2-K)") (class "Default")
      (node (ref "D2") (pin "2") (pinfunction "K_2") (pintype "passive"))
      (node (ref "R12") (pin "1") (pinfunction "1_1") (pintype "passive"))
    )
    (net (code "49") (name "Net-(D3-A)") (class "Default")
      (node (ref "D3") (pin "1") (pinfunction "A_1") (pintype "passive"))
      (node (ref "R13") (pin "2") (pinfunction "2_2") (pintype "passive"))
    )
    (net (code "50") (name "Net-(D4-K)") (class "Default")
      (node (ref "D4") (pin "2") (pinfunction "K_2") (pintype "passive"))
      (node (ref "U2") (pin "8") (pinfunction "TXD_8") (pintype "passive"))
    )
    (net (code "51") (name "Net-(D5-A)") (class "Default")
      (node (ref "D5") (pin "1") (pinfunction "A_1") (pintype "passive"))
      (node (ref "R17") (pin "2") (pinfunction "2_2") (pintype "passive"))
    )
    (net (code "52") (name "Net-(D6-A)") (class "Default")
      (node (ref "D6") (pin "1") (pinfunction "A_1") (pintype "passive"))
      (node (ref "R18") (pin "2") (pinfunction "2_2") (pintype "passive"))
    )
    (net (code "53") (name "Net-(U1-BOOT0)") (class "Default")
      (node (ref "R1") (pin "1") (pinfunction "1_1") (pintype "passive"))
      (node (ref "U1") (pin "44") (pinfunction "BOOT0_44") (pintype "passive"))
    )
    (net (code "54") (name "Net-(U1-PB2{slash}BOOT1)") (class "Default")
      (node (ref "R11") (pin "2") (pinfunction "2_2") (pintype "passive"))
      (node (ref "U1") (pin "20") (pinfunction "PB2/BOOT1_20") (pintype "passive"))
    )
    (net (code "55") (name "Net-(U2-RXD)") (class "Default")
      (node (ref "R14") (pin "2") (pinfunction "2_2") (pintype "passive"))
      (node (ref "U2") (pin "9") (pinfunction "RXD_9") (pintype "passive"))
    )
    (net (code "56") (name "Net-(U2-V3)") (class "Default")
      (node (ref "C13") (pin "2") (pinfunction "2_2") (pintype "passive"))
      (node (ref "U2") (pin "10") (pinfunction "V3_10") (pintype "passive"))
    )
    (net (code "57") (name "Net-(U3-BYPASS)") (class "Default")
      (node (ref "C17") (pin "2") (pinfunction "2_2") (pintype "passive"))
      (node (ref "U3") (pin "4") (pinfunction "BYPASS_4") (pintype "passive"))
    )
    (net (code "58") (name "Net-(USB1-CC1)") (class "Default")
      (node (ref "R15") (pin "2") (pinfunction "2_2") (pintype "passive"))
      (node (ref "USB1") (pin "A5") (pinfunction "CC1_A5") (pintype "passive"))
    )
    (net (code "59") (name "Net-(USB1-CC2)") (class "Default")
      (node (ref "R16") (pin "2") (pinfunction "2_2") (pintype "passive"))
      (node (ref "USB1") (pin "B5") (pinfunction "CC2_B5") (pintype "passive"))
    )
    (net (code "60") (name "unconnected-(1-NC(VBREF)-Pad7)") (class "Default")
      (node (ref "1") (pin "7") (pinfunction "NC(VBREF)_7") (pintype "passive"))
    )
    (net (code "61") (name "unconnected-(P4-Pad2)") (class "Default")
      (node (ref "P4") (pin "2") (pinfunction "2_2") (pintype "passive"))
    )
    (net (code "62") (name "unconnected-(SW1-Pad2)") (class "Default")
      (node (ref "SW1") (pin "2") (pinfunction "2_2") (pintype "passive"))
    )
    (net (code "63") (name "unconnected-(SW1-Pad4)") (class "Default")
      (node (ref "SW1") (pin "4") (pinfunction "4_4") (pintype "passive"))
    )
    (net (code "64") (name "unconnected-(U1-PB6-Pad42)") (class "Default")
      (node (ref "U1") (pin "42") (pinfunction "PB6_42") (pintype "passive"))
    )
    (net (code "65") (name "unconnected-(U1-PB7-Pad43)") (class "Default")
      (node (ref "U1") (pin "43") (pinfunction "PB7_43") (pintype "passive"))
    )
    (net (code "66") (name "unconnected-(U1-PB8-Pad45)") (class "Default")
      (node (ref "U1") (pin "45") (pinfunction "PB8_45") (pintype "passive"))
    )
    (net (code "67") (name "unconnected-(U1-PB9-Pad46)") (class "Default")
      (node (ref "U1") (pin "46") (pinfunction "PB9_46") (pintype "passive"))
    )
    (net (code "68") (name "unconnected-(U1-PB10-Pad21)") (class "Default")
      (node (ref "U1") (pin "21") (pinfunction "PB10_21") (pintype "passive"))
    )
    (net (code "69") (name "unconnected-(U1-PB11-Pad22)") (class "Default")
      (node (ref "U1") (pin "22") (pinfunction "PB11_22") (pintype "passive"))
    )
    (net (code "70") (name "unconnected-(U1-PB12-Pad25)") (class "Default")
      (node (ref "U1") (pin "25") (pinfunction "PB12_25") (pintype "passive"))
    )
    (net (code "71") (name "unconnected-(U1-VBAT-Pad1)") (class "Default")
      (node (ref "U1") (pin "1") (pinfunction "VBAT_1") (pintype "passive"))
    )
    (net (code "72") (name "unconnected-(U2-CTS#-Pad5)") (class "Default")
      (node (ref "U2") (pin "5") (pinfunction "CTS#_5") (pintype "passive"))
    )
    (net (code "73") (name "unconnected-(U2-RTS#-Pad4)") (class "Default")
      (node (ref "U2") (pin "4") (pinfunction "RTS#_4") (pintype "passive"))
    )
    (net (code "74") (name "unconnected-(U2-TNOW-Pad6)") (class "Default")
      (node (ref "U2") (pin "6") (pinfunction "TNOW_6") (pintype "passive"))
    )
    (net (code "75") (name "unconnected-(USB1-RX1+-PadB11)") (class "Default")
      (node (ref "USB1") (pin "B11") (pinfunction "RX1+_B11") (pintype "passive"))
    )
    (net (code "76") (name "unconnected-(USB1-RX1--PadB10)") (class "Default")
      (node (ref "USB1") (pin "B10") (pinfunction "RX1-_B10") (pintype "passive"))
    )
    (net (code "77") (name "unconnected-(USB1-RX2+-PadA11)") (class "Default")
      (node (ref "USB1") (pin "A11") (pinfunction "RX2+_A11") (pintype "passive"))
    )
    (net (code "78") (name "unconnected-(USB1-RX2--PadA10)") (class "Default")
      (node (ref "USB1") (pin "A10") (pinfunction "RX2-_A10") (pintype "passive"))
    )
    (net (code "79") (name "unconnected-(USB1-SBU1-PadA8)") (class "Default")
      (node (ref "USB1") (pin "A8") (pinfunction "SBU1_A8") (pintype "passive"))
    )
    (net (code "80") (name "unconnected-(USB1-SBU2-PadB8)") (class "Default")
      (node (ref "USB1") (pin "B8") (pinfunction "SBU2_B8") (pintype "passive"))
    )
    (net (code "81") (name "unconnected-(USB1-SH1-Pad1)") (class "Default")
      (node (ref "USB1") (pin "1") (pinfunction "SH1_1") (pintype "passive+no_connect"))
    )
    (net (code "82") (name "unconnected-(USB1-SH2-Pad2)") (class "Default")
      (node (ref "USB1") (pin "2") (pinfunction "SH2_2") (pintype "passive+no_connect"))
    )
    (net (code "83") (name "unconnected-(USB1-SH3-Pad3)") (class "Default")
      (node (ref "USB1") (pin "3") (pinfunction "SH3_3") (pintype "passive+no_connect"))
    )
    (net (code "84") (name "unconnected-(USB1-SH4-Pad4)") (class "Default")
      (node (ref "USB1") (pin "4") (pinfunction "SH4_4") (pintype "passive+no_connect"))
    )
    (net (code "85") (name "unconnected-(USB1-TX1+-PadA2)") (class "Default")
      (node (ref "USB1") (pin "A2") (pinfunction "TX1+_A2") (pintype "passive"))
    )
    (net (code "86") (name "unconnected-(USB1-TX1--PadA3)") (class "Default")
      (node (ref "USB1") (pin "A3") (pinfunction "TX1-_A3") (pintype "passive"))
    )
    (net (code "87") (name "unconnected-(USB1-TX2+-PadB2)") (class "Default")
      (node (ref "USB1") (pin "B2") (pinfunction "TX2+_B2") (pintype "passive"))
    )
    (net (code "88") (name "unconnected-(USB1-TX2--PadB3)") (class "Default")
      (node (ref "USB1") (pin "B3") (pinfunction "TX2-_B3") (pintype "passive"))
    )
  )
)
